# Raspi-TPUART_v1_1.net
KiCad netlist of a schematic drawn in EAGLE
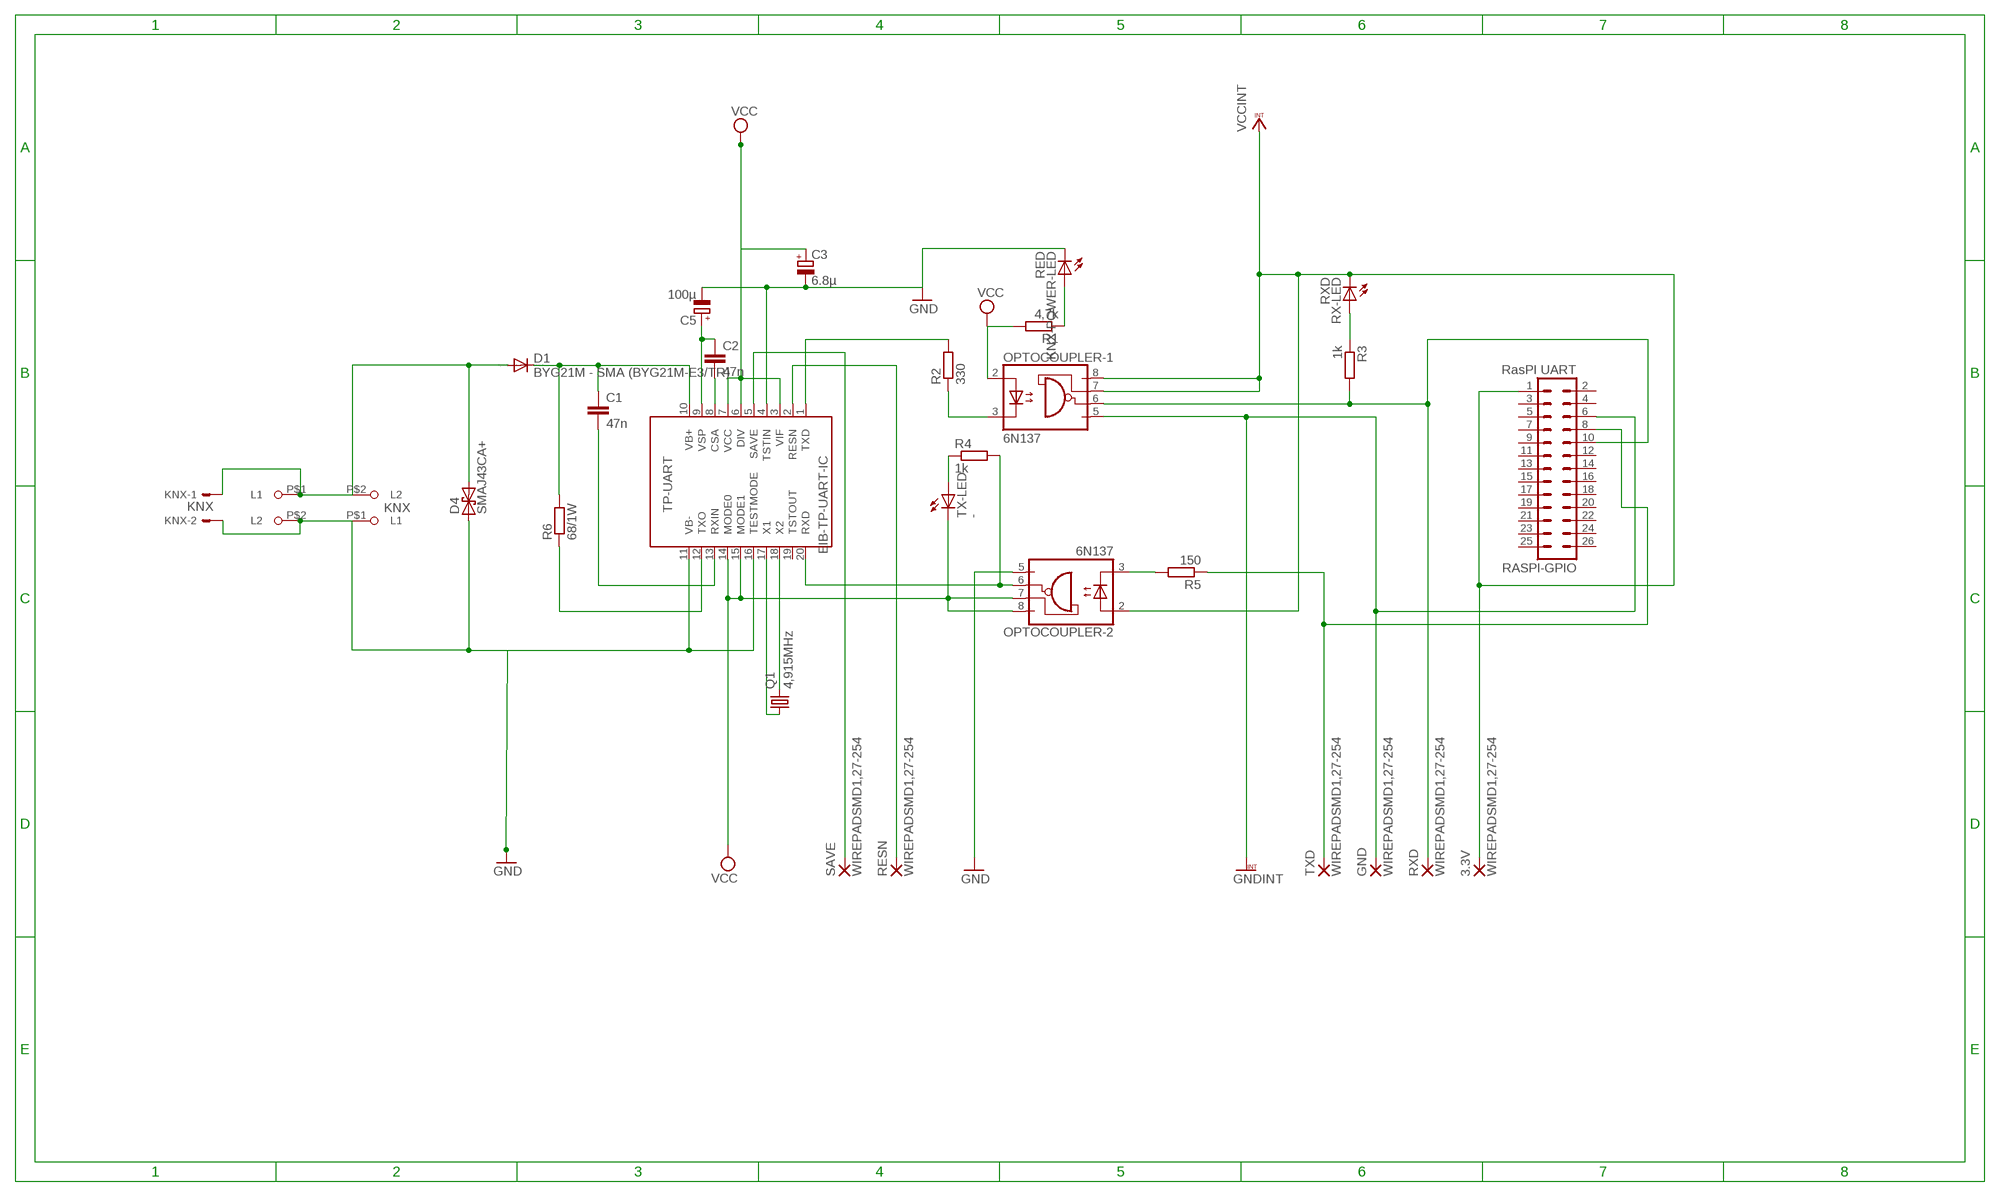
[diagram p0: schematic, sheet 1]

(export (version "E")
  (design (tool "Eeschema 10.0.6"))
  (components
    (comp (ref "3.3V")
      (value "WIREPADSMD1,27-254")
      (footprint "eagle-import:SMD1,27-2,54")
      (libsource (lib "eagle-import") (part "WIREPADSMD1,27-254"))
    )
    (comp (ref "C1")
      (value "47n")
      (footprint "eagle-import:C1206")
      (libsource (lib "eagle-import") (part "C-EUC1206"))
    )
    (comp (ref "C2")
      (value "47n")
      (footprint "eagle-import:C1206")
      (libsource (lib "eagle-import") (part "C-EUC1206"))
    )
    (comp (ref "C3")
      (value "6.8µ")
      (footprint "eagle-import:CT7343")
      (libsource (lib "eagle-import") (part "CPOL-EUCT7343"))
    )
    (comp (ref "C5")
      (value "100µ")
      (footprint "eagle-import:CT7343")
      (libsource (lib "eagle-import") (part "CPOL-EUCT7343"))
    )
    (comp (ref "D1")
      (value "BYG21M - SMA (BYG21M-E3/TR)")
      (footprint "eagle-import:SMB")
      (libsource (lib "eagle-import") (part "ES2D"))
    )
    (comp (ref "D4")
      (value "SMAJ43CA+")
      (footprint "eagle-import:DO214AA")
      (libsource (lib "eagle-import") (part "BZW04XXB"))
    )
    (comp (ref "EIB-TP-UART-IC")
      (value "TP-UART")
      (footprint "eagle-import:SOIC20")
      (libsource (lib "eagle-import") (part "TP-UART"))
    )
    (comp (ref "GND")
      (value "WIREPADSMD1,27-254")
      (footprint "eagle-import:SMD1,27-2,54")
      (libsource (lib "eagle-import") (part "WIREPADSMD1,27-254"))
    )
    (comp (ref "KNX")
      (value "KNX")
      (footprint "eagle-import:22-23-2021")
      (fields (field (name "MF") "MOLEX") (field (name "MPN") "22-23-2021"))
      (libsource (lib "eagle-import") (part "22-23-2021"))
    )
    (comp (ref "KNX-POWER-LED")
      (value "RED")
      (footprint "eagle-import:KA-3528ASYC")
      (libsource (lib "eagle-import") (part "LEDKA-3528ASYC"))
    )
    (comp (ref "KNX_WAGO_243")
      (value "243-211")
      (footprint "eagle-import:243-211")
      (libsource (lib "eagle-import") (part "243-211"))
    )
    (comp (ref "OPTOCOUPLER-1")
      (value "6N137")
      (footprint "eagle-import:DIL8-SMD")
      (libsource (lib "eagle-import") (part "6N137"))
    )
    (comp (ref "OPTOCOUPLER-2")
      (value "6N137")
      (footprint "eagle-import:DIL8-SMD")
      (libsource (lib "eagle-import") (part "6N137"))
    )
    (comp (ref "Q1")
      (value "4,915MHz")
      (footprint "eagle-import:HC49UP")
      (libsource (lib "eagle-import") (part "CRYSTALHC49UP"))
    )
    (comp (ref "R1")
      (value "4,7k")
      (footprint "eagle-import:M1206")
      (libsource (lib "eagle-import") (part "R-EU_M1206"))
    )
    (comp (ref "R2")
      (value "330")
      (footprint "eagle-import:M1206")
      (libsource (lib "eagle-import") (part "R-EU_M1206"))
    )
    (comp (ref "R3")
      (value "1k")
      (footprint "eagle-import:M1206")
      (libsource (lib "eagle-import") (part "R-EU_M1206"))
    )
    (comp (ref "R4")
      (value "1k")
      (footprint "eagle-import:M1206")
      (libsource (lib "eagle-import") (part "R-EU_M1206"))
    )
    (comp (ref "R5")
      (value "150")
      (footprint "eagle-import:M1206")
      (libsource (lib "eagle-import") (part "R-EU_M1206"))
    )
    (comp (ref "R6")
      (value "68/1W")
      (footprint "eagle-import:R2512")
      (libsource (lib "eagle-import") (part "R-EU_R2512"))
    )
    (comp (ref "RASPI-GPIO")
      (value "RasPI UART")
      (footprint "eagle-import:MA13-2")
      (libsource (lib "eagle-import") (part "MA13-2"))
    )
    (comp (ref "RESN")
      (value "WIREPADSMD1,27-254")
      (footprint "eagle-import:SMD1,27-2,54")
      (libsource (lib "eagle-import") (part "WIREPADSMD1,27-254"))
    )
    (comp (ref "RX-LED")
      (value "RXD")
      (footprint "eagle-import:KA-3528ASYC")
      (libsource (lib "eagle-import") (part "LEDKA-3528ASYC"))
    )
    (comp (ref "RXD")
      (value "WIREPADSMD1,27-254")
      (footprint "eagle-import:SMD1,27-2,54")
      (libsource (lib "eagle-import") (part "WIREPADSMD1,27-254"))
    )
    (comp (ref "SAVE")
      (value "WIREPADSMD1,27-254")
      (footprint "eagle-import:SMD1,27-2,54")
      (libsource (lib "eagle-import") (part "WIREPADSMD1,27-254"))
    )
    (comp (ref "TX-LED")
      (value "-")
      (footprint "eagle-import:KA-3528ASYC")
      (libsource (lib "eagle-import") (part "LEDKA-3528ASYC"))
    )
    (comp (ref "TXD")
      (value "WIREPADSMD1,27-254")
      (footprint "eagle-import:SMD1,27-2,54")
      (libsource (lib "eagle-import") (part "WIREPADSMD1,27-254"))
    )
    (comp (ref "U$1")
      (value "243-211")
      (footprint "eagle-import:243-211")
      (libsource (lib "eagle-import") (part "243-211"))
    )
  )
  (nets
    (net (code "1") (name "GND") (class "Default")
      (node (ref "C3") (pin "-") (pinfunction "-_-") (pintype "passive"))
      (node (ref "C5") (pin "-") (pinfunction "-_-") (pintype "passive"))
      (node (ref "D4") (pin "A") (pinfunction "1_A") (pintype "passive"))
      (node (ref "EIB-TP-UART-IC") (pin "11") (pinfunction "VB-_11") (pintype "passive"))
      (node (ref "EIB-TP-UART-IC") (pin "16") (pinfunction "TESTMODE_16") (pintype "input"))
      (node (ref "EIB-TP-UART-IC") (pin "4") (pinfunction "TSTIN_4") (pintype "bidirectional"))
      (node (ref "KNX") (pin "2") (pinfunction "S_2") (pintype "passive"))
      (node (ref "KNX-POWER-LED") (pin "C") (pinfunction "C_C") (pintype "passive"))
      (node (ref "KNX_WAGO_243") (pin "P$1") (pinfunction "L1_P$1") (pintype "bidirectional"))
      (node (ref "OPTOCOUPLER-2") (pin "5") (pinfunction "GND_5") (pintype "passive"))
      (node (ref "U$1") (pin "P$2") (pinfunction "L2_P$2") (pintype "bidirectional"))
    )
    (net (code "2") (name "GNDINT") (class "Default")
      (node (ref "GND") (pin "1") (pinfunction "P_1") (pintype "passive"))
      (node (ref "OPTOCOUPLER-1") (pin "5") (pinfunction "GND_5") (pintype "passive"))
      (node (ref "RASPI-GPIO") (pin "6") (pinfunction "6_6") (pintype "passive"))
    )
    (net (code "3") (name "Net-(D4-2)") (class "Default")
      (node (ref "D1") (pin "A") (pinfunction "A_A") (pintype "passive"))
      (node (ref "D4") (pin "C") (pinfunction "2_C") (pintype "passive"))
      (node (ref "KNX") (pin "1") (pinfunction "S_1") (pintype "passive"))
      (node (ref "KNX_WAGO_243") (pin "P$2") (pinfunction "L2_P$2") (pintype "bidirectional"))
      (node (ref "U$1") (pin "P$1") (pinfunction "L1_P$1") (pintype "bidirectional"))
    )
    (net (code "4") (name "Net-(EIB-TP-UART-IC-CSA)") (class "Default")
      (node (ref "C2") (pin "2") (pinfunction "2_2") (pintype "passive"))
      (node (ref "EIB-TP-UART-IC") (pin "8") (pinfunction "CSA_8") (pintype "passive"))
    )
    (net (code "5") (name "Net-(EIB-TP-UART-IC-RESN)") (class "Default")
      (node (ref "EIB-TP-UART-IC") (pin "2") (pinfunction "RESN_2") (pintype "bidirectional"))
      (node (ref "RESN") (pin "1") (pinfunction "P_1") (pintype "passive"))
    )
    (net (code "6") (name "Net-(EIB-TP-UART-IC-RXD)") (class "Default")
      (node (ref "EIB-TP-UART-IC") (pin "20") (pinfunction "RXD_20") (pintype "input"))
      (node (ref "OPTOCOUPLER-2") (pin "6") (pinfunction "VO_6") (pintype "passive"))
      (node (ref "R4") (pin "2") (pinfunction "2_2") (pintype "passive"))
    )
    (net (code "7") (name "Net-(EIB-TP-UART-IC-RXIN)") (class "Default")
      (node (ref "C1") (pin "2") (pinfunction "2_2") (pintype "passive"))
      (node (ref "EIB-TP-UART-IC") (pin "13") (pinfunction "RXIN_13") (pintype "input"))
    )
    (net (code "8") (name "Net-(EIB-TP-UART-IC-SAVE)") (class "Default")
      (node (ref "EIB-TP-UART-IC") (pin "5") (pinfunction "SAVE_5") (pintype "open_collector"))
      (node (ref "SAVE") (pin "1") (pinfunction "P_1") (pintype "passive"))
    )
    (net (code "9") (name "Net-(EIB-TP-UART-IC-TXD)") (class "Default")
      (node (ref "EIB-TP-UART-IC") (pin "1") (pinfunction "TXD_1") (pintype "output"))
      (node (ref "R2") (pin "2") (pinfunction "2_2") (pintype "passive"))
    )
    (net (code "10") (name "Net-(EIB-TP-UART-IC-TXO)") (class "Default")
      (node (ref "EIB-TP-UART-IC") (pin "12") (pinfunction "TXO_12") (pintype "output"))
      (node (ref "R6") (pin "1") (pinfunction "1_1") (pintype "passive"))
    )
    (net (code "11") (name "Net-(EIB-TP-UART-IC-VB+)") (class "Default")
      (node (ref "C1") (pin "1") (pinfunction "1_1") (pintype "passive"))
      (node (ref "D1") (pin "C") (pinfunction "C_C") (pintype "passive"))
      (node (ref "EIB-TP-UART-IC") (pin "10") (pinfunction "VB+_10") (pintype "passive"))
      (node (ref "R6") (pin "2") (pinfunction "2_2") (pintype "passive"))
    )
    (net (code "12") (name "Net-(EIB-TP-UART-IC-VSP)") (class "Default")
      (node (ref "C2") (pin "1") (pinfunction "1_1") (pintype "passive"))
      (node (ref "C5") (pin "+") (pinfunction "+_+") (pintype "passive"))
      (node (ref "EIB-TP-UART-IC") (pin "9") (pinfunction "VSP_9") (pintype "passive"))
    )
    (net (code "13") (name "Net-(EIB-TP-UART-IC-X1)") (class "Default")
      (node (ref "EIB-TP-UART-IC") (pin "17") (pinfunction "X1_17") (pintype "passive"))
      (node (ref "Q1") (pin "1") (pinfunction "1_1") (pintype "passive"))
    )
    (net (code "14") (name "Net-(EIB-TP-UART-IC-X2)") (class "Default")
      (node (ref "EIB-TP-UART-IC") (pin "18") (pinfunction "X2_18") (pintype "passive"))
      (node (ref "Q1") (pin "2") (pinfunction "2_2") (pintype "passive"))
    )
    (net (code "15") (name "Net-(KNX-POWER-LED-PadA)") (class "Default")
      (node (ref "KNX-POWER-LED") (pin "A") (pinfunction "A_A") (pintype "passive"))
      (node (ref "R1") (pin "1") (pinfunction "1_1") (pintype "passive"))
    )
    (net (code "16") (name "Net-(OPTOCOUPLER-1-C)") (class "Default")
      (node (ref "OPTOCOUPLER-1") (pin "3") (pinfunction "C_3") (pintype "passive"))
      (node (ref "R2") (pin "1") (pinfunction "1_1") (pintype "passive"))
    )
    (net (code "17") (name "Net-(OPTOCOUPLER-1-VO)") (class "Default")
      (node (ref "OPTOCOUPLER-1") (pin "6") (pinfunction "VO_6") (pintype "passive"))
      (node (ref "R3") (pin "2") (pinfunction "2_2") (pintype "passive"))
      (node (ref "RASPI-GPIO") (pin "10") (pinfunction "10_10") (pintype "passive"))
      (node (ref "RXD") (pin "1") (pinfunction "P_1") (pintype "passive"))
    )
    (net (code "18") (name "Net-(OPTOCOUPLER-2-C)") (class "Default")
      (node (ref "OPTOCOUPLER-2") (pin "3") (pinfunction "C_3") (pintype "passive"))
      (node (ref "R5") (pin "2") (pinfunction "2_2") (pintype "passive"))
    )
    (net (code "19") (name "Net-(R3-Pad1)") (class "Default")
      (node (ref "R3") (pin "1") (pinfunction "1_1") (pintype "passive"))
      (node (ref "RX-LED") (pin "A") (pinfunction "A_A") (pintype "passive"))
    )
    (net (code "20") (name "Net-(R4-Pad1)") (class "Default")
      (node (ref "R4") (pin "1") (pinfunction "1_1") (pintype "passive"))
      (node (ref "TX-LED") (pin "A") (pinfunction "A_A") (pintype "passive"))
    )
    (net (code "21") (name "Net-(TXD-P)") (class "Default")
      (node (ref "R5") (pin "1") (pinfunction "1_1") (pintype "passive"))
      (node (ref "RASPI-GPIO") (pin "8") (pinfunction "8_8") (pintype "passive"))
      (node (ref "TXD") (pin "1") (pinfunction "P_1") (pintype "passive"))
    )
    (net (code "22") (name "VCC") (class "Default")
      (node (ref "C3") (pin "+") (pinfunction "+_+") (pintype "passive"))
      (node (ref "EIB-TP-UART-IC") (pin "14") (pinfunction "MODE0_14") (pintype "input"))
      (node (ref "EIB-TP-UART-IC") (pin "15") (pinfunction "MODE1_15") (pintype "input"))
      (node (ref "EIB-TP-UART-IC") (pin "3") (pinfunction "VIF_3") (pintype "input"))
      (node (ref "EIB-TP-UART-IC") (pin "6") (pinfunction "DIV_6") (pintype "input"))
      (node (ref "EIB-TP-UART-IC") (pin "7") (pinfunction "VCC_7") (pintype "output"))
      (node (ref "OPTOCOUPLER-1") (pin "2") (pinfunction "A_2") (pintype "passive"))
      (node (ref "OPTOCOUPLER-2") (pin "7") (pinfunction "VE_7") (pintype "passive"))
      (node (ref "OPTOCOUPLER-2") (pin "8") (pinfunction "VCC_8") (pintype "passive"))
      (node (ref "R1") (pin "2") (pinfunction "2_2") (pintype "passive"))
      (node (ref "TX-LED") (pin "C") (pinfunction "C_C") (pintype "passive"))
    )
    (net (code "23") (name "VCCINT") (class "Default")
      (node (ref "3.3V") (pin "1") (pinfunction "P_1") (pintype "passive"))
      (node (ref "OPTOCOUPLER-1") (pin "7") (pinfunction "VE_7") (pintype "passive"))
      (node (ref "OPTOCOUPLER-1") (pin "8") (pinfunction "VCC_8") (pintype "passive"))
      (node (ref "OPTOCOUPLER-2") (pin "2") (pinfunction "A_2") (pintype "passive"))
      (node (ref "RASPI-GPIO") (pin "1") (pinfunction "1_1") (pintype "passive"))
      (node (ref "RX-LED") (pin "C") (pinfunction "C_C") (pintype "passive"))
    )
    (net (code "24") (name "unconnected-(EIB-TP-UART-IC-TSTOUT-Pad19)") (class "Default")
      (node (ref "EIB-TP-UART-IC") (pin "19") (pinfunction "TSTOUT_19") (pintype "output"))
    )
    (net (code "25") (name "unconnected-(RASPI-GPIO-Pad2)") (class "Default")
      (node (ref "RASPI-GPIO") (pin "2") (pinfunction "2_2") (pintype "passive"))
    )
    (net (code "26") (name "unconnected-(RASPI-GPIO-Pad3)") (class "Default")
      (node (ref "RASPI-GPIO") (pin "3") (pinfunction "3_3") (pintype "passive"))
    )
    (net (code "27") (name "unconnected-(RASPI-GPIO-Pad4)") (class "Default")
      (node (ref "RASPI-GPIO") (pin "4") (pinfunction "4_4") (pintype "passive"))
    )
    (net (code "28") (name "unconnected-(RASPI-GPIO-Pad5)") (class "Default")
      (node (ref "RASPI-GPIO") (pin "5") (pinfunction "5_5") (pintype "passive"))
    )
    (net (code "29") (name "unconnected-(RASPI-GPIO-Pad7)") (class "Default")
      (node (ref "RASPI-GPIO") (pin "7") (pinfunction "7_7") (pintype "passive"))
    )
    (net (code "30") (name "unconnected-(RASPI-GPIO-Pad9)") (class "Default")
      (node (ref "RASPI-GPIO") (pin "9") (pinfunction "9_9") (pintype "passive"))
    )
    (net (code "31") (name "unconnected-(RASPI-GPIO-Pad11)") (class "Default")
      (node (ref "RASPI-GPIO") (pin "11") (pinfunction "11_11") (pintype "passive"))
    )
    (net (code "32") (name "unconnected-(RASPI-GPIO-Pad12)") (class "Default")
      (node (ref "RASPI-GPIO") (pin "12") (pinfunction "12_12") (pintype "passive"))
    )
    (net (code "33") (name "unconnected-(RASPI-GPIO-Pad13)") (class "Default")
      (node (ref "RASPI-GPIO") (pin "13") (pinfunction "13_13") (pintype "passive"))
    )
    (net (code "34") (name "unconnected-(RASPI-GPIO-Pad14)") (class "Default")
      (node (ref "RASPI-GPIO") (pin "14") (pinfunction "14_14") (pintype "passive"))
    )
    (net (code "35") (name "unconnected-(RASPI-GPIO-Pad15)") (class "Default")
      (node (ref "RASPI-GPIO") (pin "15") (pinfunction "15_15") (pintype "passive"))
    )
    (net (code "36") (name "unconnected-(RASPI-GPIO-Pad16)") (class "Default")
      (node (ref "RASPI-GPIO") (pin "16") (pinfunction "16_16") (pintype "passive"))
    )
    (net (code "37") (name "unconnected-(RASPI-GPIO-Pad17)") (class "Default")
      (node (ref "RASPI-GPIO") (pin "17") (pinfunction "17_17") (pintype "passive"))
    )
    (net (code "38") (name "unconnected-(RASPI-GPIO-Pad18)") (class "Default")
      (node (ref "RASPI-GPIO") (pin "18") (pinfunction "18_18") (pintype "passive"))
    )
    (net (code "39") (name "unconnected-(RASPI-GPIO-Pad19)") (class "Default")
      (node (ref "RASPI-GPIO") (pin "19") (pinfunction "19_19") (pintype "passive"))
    )
    (net (code "40") (name "unconnected-(RASPI-GPIO-Pad20)") (class "Default")
      (node (ref "RASPI-GPIO") (pin "20") (pinfunction "20_20") (pintype "passive"))
    )
    (net (code "41") (name "unconnected-(RASPI-GPIO-Pad21)") (class "Default")
      (node (ref "RASPI-GPIO") (pin "21") (pinfunction "21_21") (pintype "passive"))
    )
    (net (code "42") (name "unconnected-(RASPI-GPIO-Pad22)") (class "Default")
      (node (ref "RASPI-GPIO") (pin "22") (pinfunction "22_22") (pintype "passive"))
    )
    (net (code "43") (name "unconnected-(RASPI-GPIO-Pad23)") (class "Default")
      (node (ref "RASPI-GPIO") (pin "23") (pinfunction "23_23") (pintype "passive"))
    )
    (net (code "44") (name "unconnected-(RASPI-GPIO-Pad24)") (class "Default")
      (node (ref "RASPI-GPIO") (pin "24") (pinfunction "24_24") (pintype "passive"))
    )
    (net (code "45") (name "unconnected-(RASPI-GPIO-Pad25)") (class "Default")
      (node (ref "RASPI-GPIO") (pin "25") (pinfunction "25_25") (pintype "passive"))
    )
    (net (code "46") (name "unconnected-(RASPI-GPIO-Pad26)") (class "Default")
      (node (ref "RASPI-GPIO") (pin "26") (pinfunction "26_26") (pintype "passive"))
    )
  )
)
